# RTC.net
KiCad netlist of a schematic drawn in Altium Designer
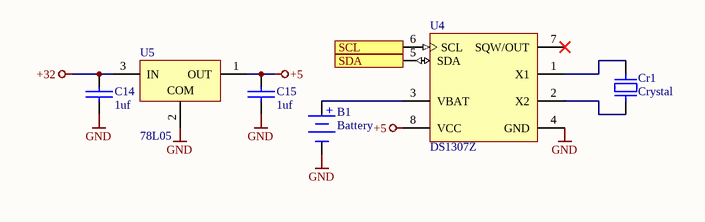
[diagram p0: RTC.SchDoc]

(export (version "E")
  (design (tool "Eeschema 10.0.6"))
  (components
    (comp (ref "B1")
      (value "Battery")
      (footprint "20mm Coine Battery Holder")
      (libsource (lib "E-component") (part "Battery"))
    )
    (comp (ref "C14")
      (value "1uf")
      (footprint "cap_0805_A")
      (description "octopart or digikey description!")
      (libsource (lib "E-component") (part "Capacitor"))
    )
    (comp (ref "C15")
      (value "1uf")
      (footprint "cap_0805_A")
      (description "octopart or digikey description!")
      (libsource (lib "E-component") (part "Capacitor"))
    )
    (comp (ref "Cr1")
      (value "Crystal")
      (footprint "Crystal MC-405")
      (libsource (lib "E-component") (part "Crystal"))
    )
    (comp (ref "U4")
      (value "DS1307Z")
      (footprint "SOIC_8_Maxim_M")
      (description "64 x 8, Serial, I2C Real-Time Clock, 5.0V, 8-Pin SO, 0 to 70 degC")
      (libsource (lib "E-component") (part "DS1307Z"))
    )
    (comp (ref "U5")
      (value "78L05")
      (footprint "78L05")
      (fields (field (name "PARTNUMBER") "UA78L05ACLPR") (field (name "MANUFACTURER") "Texas Instruments"))
      (libsource (lib "E-component") (part "78L05"))
    )
  )
  (nets
    (net (code "1") (name "+5") (class "Default")
      (node (ref "C15") (pin "1") (pinfunction "1_1") (pintype "passive"))
      (node (ref "U4") (pin "8") (pinfunction "VCC_8") (pintype "power_in"))
      (node (ref "U5") (pin "1") (pinfunction "OUT_1") (pintype "power_in"))
    )
    (net (code "2") (name "+32") (class "Default")
      (node (ref "C14") (pin "1") (pinfunction "1_1") (pintype "passive"))
      (node (ref "U5") (pin "3") (pinfunction "IN_3") (pintype "power_in"))
    )
    (net (code "3") (name "/SCL") (class "Default")
      (node (ref "U4") (pin "6") (pinfunction "SCL_6") (pintype "input"))
    )
    (net (code "4") (name "/SDA") (class "Default")
      (node (ref "U4") (pin "5") (pinfunction "SDA_5") (pintype "bidirectional"))
    )
    (net (code "5") (name "GND") (class "Default")
      (node (ref "B1") (pin "2") (pinfunction "-_2") (pintype "passive"))
      (node (ref "C14") (pin "2") (pinfunction "2_2") (pintype "passive"))
      (node (ref "C15") (pin "2") (pinfunction "2_2") (pintype "passive"))
      (node (ref "U4") (pin "4") (pinfunction "GND_4") (pintype "power_in"))
      (node (ref "U5") (pin "2") (pinfunction "COM_2") (pintype "power_in"))
    )
    (net (code "6") (name "Net-(B1-+)") (class "Default")
      (node (ref "B1") (pin "1") (pinfunction "+_1") (pintype "passive"))
      (node (ref "U4") (pin "3") (pinfunction "VBAT_3") (pintype "power_in"))
    )
    (net (code "7") (name "Net-(U4-X1)") (class "Default")
      (node (ref "Cr1") (pin "2") (pinfunction "2_2") (pintype "passive"))
      (node (ref "U4") (pin "1") (pinfunction "X1_1") (pintype "passive"))
    )
    (net (code "8") (name "Net-(U4-X2)") (class "Default")
      (node (ref "Cr1") (pin "1") (pinfunction "1_1") (pintype "passive"))
      (node (ref "U4") (pin "2") (pinfunction "X2_2") (pintype "passive"))
    )
    (net (code "9") (name "unconnected-(U4-SQW{slash}OUT-Pad7)") (class "Default")
      (node (ref "U4") (pin "7") (pinfunction "SQW/OUT_7") (pintype "open_collector+no_connect"))
    )
  )
)
